# TR_Switch.net
KiCad netlist of a schematic drawn in EAGLE
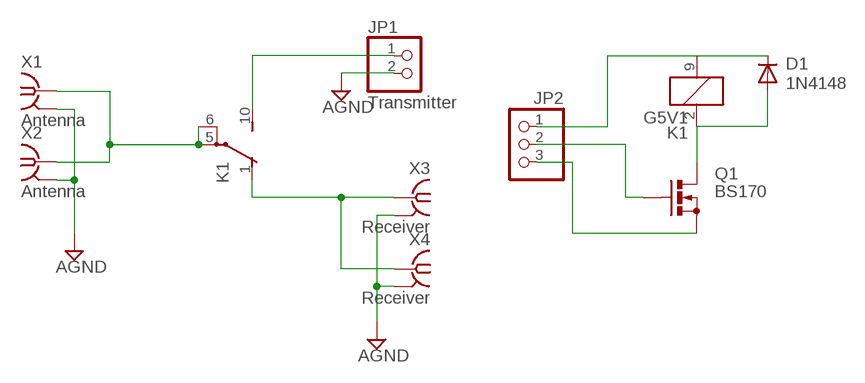
[diagram p0: schematic, sheet 1]

(export (version "E")
  (design (tool "Eeschema 10.0.6"))
  (components
    (comp (ref "D1")
      (value "1N4148")
      (footprint "eagle-import:DO35-7")
      (libsource (lib "eagle-import") (part "1N4148DO35-7"))
    )
    (comp (ref "JP1")
      (value "Transmitter")
      (footprint "eagle-import:1X02")
      (libsource (lib "eagle-import") (part "PINHD-1X2"))
    )
    (comp (ref "JP2")
      (value "PINHD-1X3")
      (footprint "eagle-import:1X03")
      (libsource (lib "eagle-import") (part "PINHD-1X3"))
    )
    (comp (ref "K1")
      (value "G5V1")
      (footprint "eagle-import:G5V1")
      (fields (field (name "MPN") "G5V-1-DC24"))
      (libsource (lib "eagle-import") (part "G5V1"))
    )
    (comp (ref "Q1")
      (value "BS170")
      (footprint "eagle-import:SOT54E")
      (libsource (lib "eagle-import") (part "BS170"))
    )
    (comp (ref "X1")
      (value "Antenna")
      (footprint "eagle-import:J502-ND-142-0711-821_826")
      (fields (field (name "MF") "JOHNSON COMPONENTS") (field (name "MPN") "142-0711-821"))
      (libsource (lib "eagle-import") (part "SMA-142-0711-821/826"))
    )
    (comp (ref "X2")
      (value "Antenna")
      (footprint "eagle-import:BU-SMA-V")
      (libsource (lib "eagle-import") (part "BU-SMA-V"))
    )
    (comp (ref "X3")
      (value "Receiver")
      (footprint "eagle-import:J502-ND-142-0711-821_826")
      (fields (field (name "MF") "JOHNSON COMPONENTS") (field (name "MPN") "142-0711-821"))
      (libsource (lib "eagle-import") (part "SMA-142-0711-821/826"))
    )
    (comp (ref "X4")
      (value "Receiver")
      (footprint "eagle-import:BU-SMA-V")
      (libsource (lib "eagle-import") (part "BU-SMA-V"))
    )
  )
  (nets
    (net (code "1") (name "AGND") (class "Default")
      (node (ref "JP1") (pin "2") (pinfunction "2_2") (pintype "passive"))
      (node (ref "X1") (pin "G@1") (pinfunction "2_G@1") (pintype "passive"))
      (node (ref "X1") (pin "G@2") (pinfunction "2_G@2") (pintype "passive"))
      (node (ref "X1") (pin "G@3") (pinfunction "2_G@3") (pintype "passive"))
      (node (ref "X1") (pin "G@4") (pinfunction "2_G@4") (pintype "passive"))
      (node (ref "X2") (pin "2") (pinfunction "2_2") (pintype "passive"))
      (node (ref "X2") (pin "3") (pinfunction "2_3") (pintype "passive"))
      (node (ref "X2") (pin "4") (pinfunction "2_4") (pintype "passive"))
      (node (ref "X2") (pin "5") (pinfunction "2_5") (pintype "passive"))
      (node (ref "X3") (pin "G@1") (pinfunction "2_G@1") (pintype "passive"))
      (node (ref "X3") (pin "G@2") (pinfunction "2_G@2") (pintype "passive"))
      (node (ref "X3") (pin "G@3") (pinfunction "2_G@3") (pintype "passive"))
      (node (ref "X3") (pin "G@4") (pinfunction "2_G@4") (pintype "passive"))
      (node (ref "X4") (pin "2") (pinfunction "2_2") (pintype "passive"))
      (node (ref "X4") (pin "3") (pinfunction "2_3") (pintype "passive"))
      (node (ref "X4") (pin "4") (pinfunction "2_4") (pintype "passive"))
      (node (ref "X4") (pin "5") (pinfunction "2_5") (pintype "passive"))
    )
    (net (code "2") (name "Net-(JP2-Pad2)") (class "Default")
      (node (ref "JP2") (pin "2") (pinfunction "2_2") (pintype "passive"))
      (node (ref "Q1") (pin "G") (pinfunction "G_G") (pintype "passive"))
    )
    (net (code "3") (name "Net-(JP2-Pad3)") (class "Default")
      (node (ref "JP2") (pin "3") (pinfunction "3_3") (pintype "passive"))
      (node (ref "Q1") (pin "S") (pinfunction "S_S") (pintype "passive"))
    )
    (net (code "4") (name "Net-(K1A-1)") (class "Default")
      (node (ref "D1") (pin "A") (pinfunction "A_A") (pintype "passive"))
      (node (ref "K1") (pin "2") (pinfunction "1_2") (pintype "passive"))
      (node (ref "Q1") (pin "D") (pinfunction "D_D") (pintype "passive"))
    )
    (net (code "5") (name "Net-(K1A-2)") (class "Default")
      (node (ref "D1") (pin "C") (pinfunction "C_C") (pintype "passive"))
      (node (ref "JP2") (pin "1") (pinfunction "1_1") (pintype "passive"))
      (node (ref "K1") (pin "9") (pinfunction "2_9") (pintype "passive"))
    )
    (net (code "6") (name "Net-(K1B-O)") (class "Default")
      (node (ref "K1") (pin "1") (pinfunction "O_1") (pintype "passive"))
      (node (ref "X3") (pin "1") (pinfunction "1_1") (pintype "passive"))
      (node (ref "X4") (pin "1") (pinfunction "1_1") (pintype "passive"))
    )
    (net (code "7") (name "Net-(K1B-P-Pad5)") (class "Default")
      (node (ref "K1") (pin "5") (pinfunction "P_5") (pintype "passive"))
      (node (ref "K1") (pin "6") (pinfunction "P_6") (pintype "passive"))
      (node (ref "X1") (pin "1") (pinfunction "1_1") (pintype "passive"))
      (node (ref "X2") (pin "1") (pinfunction "1_1") (pintype "passive"))
    )
    (net (code "8") (name "Net-(K1B-S)") (class "Default")
      (node (ref "JP1") (pin "1") (pinfunction "1_1") (pintype "passive"))
      (node (ref "K1") (pin "10") (pinfunction "S_10") (pintype "passive"))
    )
  )
)
